# REACTION-CIRCUIT-DISPLAY.net
KiCad netlist of a schematic drawn in Altium Designer
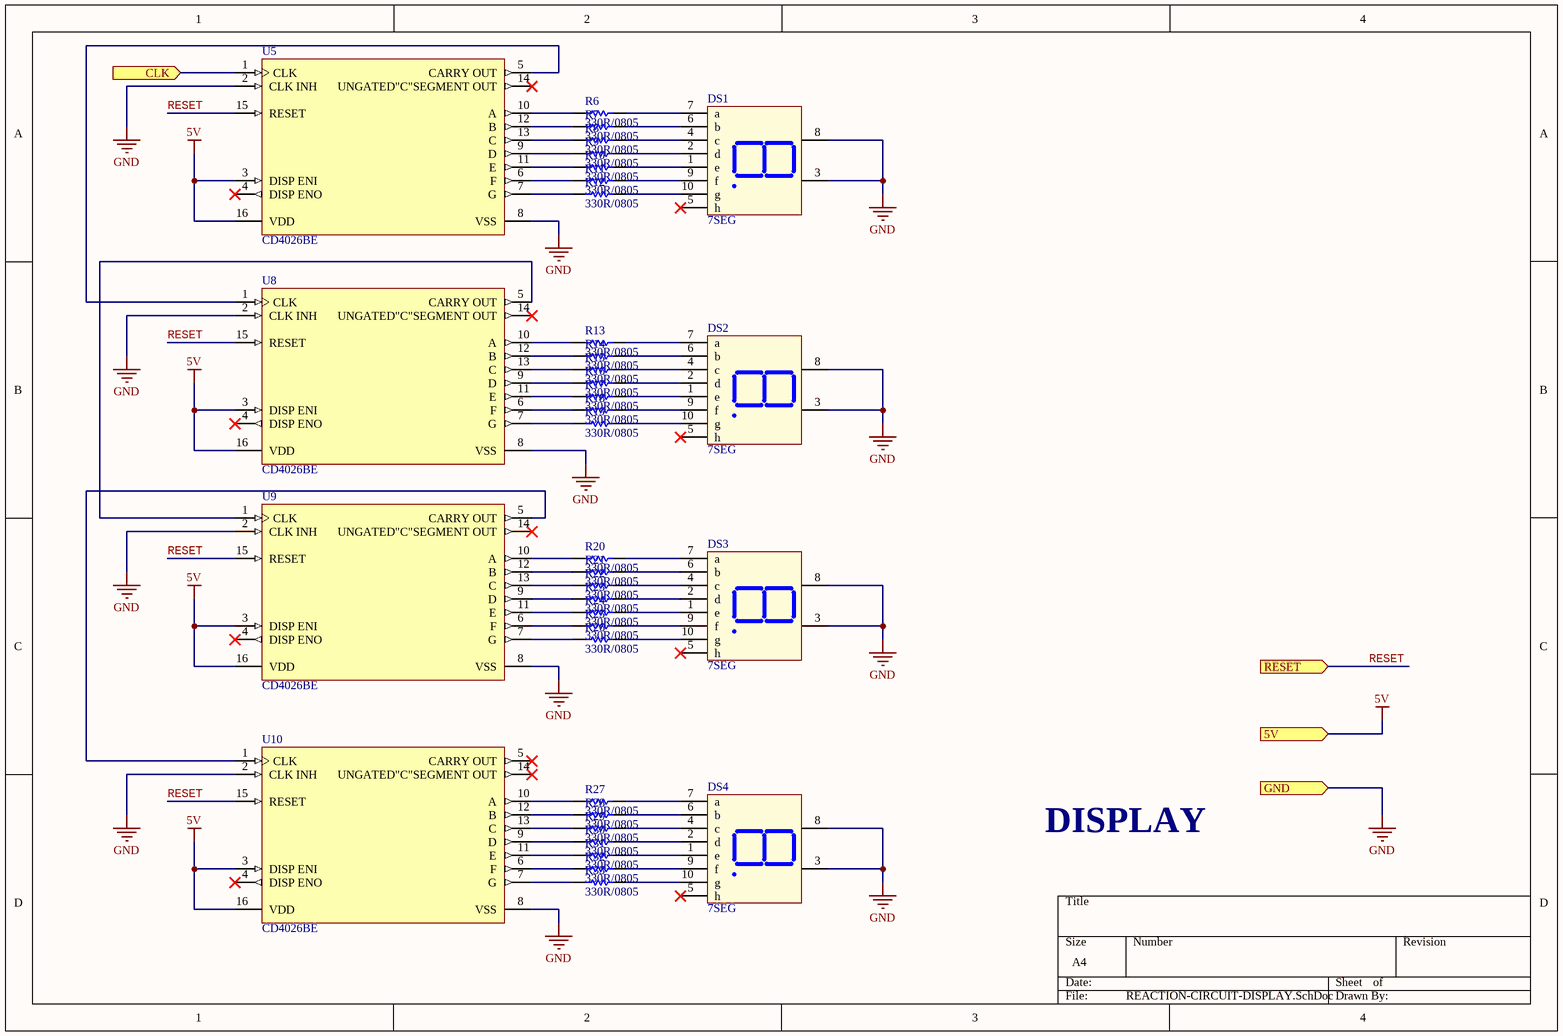
[diagram p0: REACTION-CIRCUIT-DISPLAY.SchDoc]

(export (version "E")
  (design (tool "Eeschema 10.0.6"))
  (components
    (comp (ref "DS1")
      (value "7SEG")
      (footprint "LED7SEG-1-0.56")
      (description "14.2 mm General Purpose Blue 7-Segment Display: CC, RH DP, Gray Surface")
      (fields (field (name "PUBLISHER") "Altium Limited"))
      (libsource (lib "LIBRARY_MuaLinhKien") (part "LED7SEG-1"))
    )
    (comp (ref "DS2")
      (value "7SEG")
      (footprint "LED7SEG-1-0.56")
      (description "14.2 mm General Purpose Blue 7-Segment Display: CC, RH DP, Gray Surface")
      (fields (field (name "PUBLISHER") "Altium Limited"))
      (libsource (lib "LIBRARY_MuaLinhKien") (part "LED7SEG-1"))
    )
    (comp (ref "DS3")
      (value "7SEG")
      (footprint "LED7SEG-1-0.56")
      (description "14.2 mm General Purpose Blue 7-Segment Display: CC, RH DP, Gray Surface")
      (fields (field (name "PUBLISHER") "Altium Limited"))
      (libsource (lib "LIBRARY_MuaLinhKien") (part "LED7SEG-1"))
    )
    (comp (ref "DS4")
      (value "7SEG")
      (footprint "LED7SEG-1-0.56")
      (description "14.2 mm General Purpose Blue 7-Segment Display: CC, RH DP, Gray Surface")
      (fields (field (name "PUBLISHER") "Altium Limited"))
      (libsource (lib "LIBRARY_MuaLinhKien") (part "LED7SEG-1"))
    )
    (comp (ref "R6")
      (value "330R/0805")
      (footprint "Res 0805(2012)")
      (description "Resistor 0805")
      (libsource (lib "Duc") (part "Resistor 0805"))
    )
    (comp (ref "R7")
      (value "330R/0805")
      (footprint "Res 0805(2012)")
      (description "Resistor 0805")
      (libsource (lib "Duc") (part "Resistor 0805"))
    )
    (comp (ref "R8")
      (value "330R/0805")
      (footprint "Res 0805(2012)")
      (description "Resistor 0805")
      (libsource (lib "Duc") (part "Resistor 0805"))
    )
    (comp (ref "R9")
      (value "330R/0805")
      (footprint "Res 0805(2012)")
      (description "Resistor 0805")
      (libsource (lib "Duc") (part "Resistor 0805"))
    )
    (comp (ref "R10")
      (value "330R/0805")
      (footprint "Res 0805(2012)")
      (description "Resistor 0805")
      (libsource (lib "Duc") (part "Resistor 0805"))
    )
    (comp (ref "R11")
      (value "330R/0805")
      (footprint "Res 0805(2012)")
      (description "Resistor 0805")
      (libsource (lib "Duc") (part "Resistor 0805"))
    )
    (comp (ref "R12")
      (value "330R/0805")
      (footprint "Res 0805(2012)")
      (description "Resistor 0805")
      (libsource (lib "Duc") (part "Resistor 0805"))
    )
    (comp (ref "R13")
      (value "330R/0805")
      (footprint "Res 0805(2012)")
      (description "Resistor 0805")
      (libsource (lib "Duc") (part "Resistor 0805"))
    )
    (comp (ref "R14")
      (value "330R/0805")
      (footprint "Res 0805(2012)")
      (description "Resistor 0805")
      (libsource (lib "Duc") (part "Resistor 0805"))
    )
    (comp (ref "R15")
      (value "330R/0805")
      (footprint "Res 0805(2012)")
      (description "Resistor 0805")
      (libsource (lib "Duc") (part "Resistor 0805"))
    )
    (comp (ref "R16")
      (value "330R/0805")
      (footprint "Res 0805(2012)")
      (description "Resistor 0805")
      (libsource (lib "Duc") (part "Resistor 0805"))
    )
    (comp (ref "R17")
      (value "330R/0805")
      (footprint "Res 0805(2012)")
      (description "Resistor 0805")
      (libsource (lib "Duc") (part "Resistor 0805"))
    )
    (comp (ref "R18")
      (value "330R/0805")
      (footprint "Res 0805(2012)")
      (description "Resistor 0805")
      (libsource (lib "Duc") (part "Resistor 0805"))
    )
    (comp (ref "R19")
      (value "330R/0805")
      (footprint "Res 0805(2012)")
      (description "Resistor 0805")
      (libsource (lib "Duc") (part "Resistor 0805"))
    )
    (comp (ref "R20")
      (value "330R/0805")
      (footprint "Res 0805(2012)")
      (description "Resistor 0805")
      (libsource (lib "Duc") (part "Resistor 0805"))
    )
    (comp (ref "R21")
      (value "330R/0805")
      (footprint "Res 0805(2012)")
      (description "Resistor 0805")
      (libsource (lib "Duc") (part "Resistor 0805"))
    )
    (comp (ref "R22")
      (value "330R/0805")
      (footprint "Res 0805(2012)")
      (description "Resistor 0805")
      (libsource (lib "Duc") (part "Resistor 0805"))
    )
    (comp (ref "R23")
      (value "330R/0805")
      (footprint "Res 0805(2012)")
      (description "Resistor 0805")
      (libsource (lib "Duc") (part "Resistor 0805"))
    )
    (comp (ref "R24")
      (value "330R/0805")
      (footprint "Res 0805(2012)")
      (description "Resistor 0805")
      (libsource (lib "Duc") (part "Resistor 0805"))
    )
    (comp (ref "R25")
      (value "330R/0805")
      (footprint "Res 0805(2012)")
      (description "Resistor 0805")
      (libsource (lib "Duc") (part "Resistor 0805"))
    )
    (comp (ref "R26")
      (value "330R/0805")
      (footprint "Res 0805(2012)")
      (description "Resistor 0805")
      (libsource (lib "Duc") (part "Resistor 0805"))
    )
    (comp (ref "R27")
      (value "330R/0805")
      (footprint "Res 0805(2012)")
      (description "Resistor 0805")
      (libsource (lib "Duc") (part "Resistor 0805"))
    )
    (comp (ref "R28")
      (value "330R/0805")
      (footprint "Res 0805(2012)")
      (description "Resistor 0805")
      (libsource (lib "Duc") (part "Resistor 0805"))
    )
    (comp (ref "R29")
      (value "330R/0805")
      (footprint "Res 0805(2012)")
      (description "Resistor 0805")
      (libsource (lib "Duc") (part "Resistor 0805"))
    )
    (comp (ref "R30")
      (value "330R/0805")
      (footprint "Res 0805(2012)")
      (description "Resistor 0805")
      (libsource (lib "Duc") (part "Resistor 0805"))
    )
    (comp (ref "R31")
      (value "330R/0805")
      (footprint "Res 0805(2012)")
      (description "Resistor 0805")
      (libsource (lib "Duc") (part "Resistor 0805"))
    )
    (comp (ref "R32")
      (value "330R/0805")
      (footprint "Res 0805(2012)")
      (description "Resistor 0805")
      (libsource (lib "Duc") (part "Resistor 0805"))
    )
    (comp (ref "R33")
      (value "330R/0805")
      (footprint "Res 0805(2012)")
      (description "Resistor 0805")
      (libsource (lib "Duc") (part "Resistor 0805"))
    )
    (comp (ref "U5")
      (value "CD4026BE")
      (footprint "N0016A")
      (fields
        (field (name "MANUFACTURER") "Texas Instruments")
        (field (name "GENERIC PART NUMBER") "CD4026B")
      )
      (libsource (lib "Altium Content Vault") (part "TI-CD4026B-16"))
    )
    (comp (ref "U8")
      (value "CD4026BE")
      (footprint "N0016A")
      (fields
        (field (name "MANUFACTURER") "Texas Instruments")
        (field (name "GENERIC PART NUMBER") "CD4026B")
      )
      (libsource (lib "Altium Content Vault") (part "TI-CD4026B-16"))
    )
    (comp (ref "U9")
      (value "CD4026BE")
      (footprint "N0016A")
      (fields
        (field (name "MANUFACTURER") "Texas Instruments")
        (field (name "GENERIC PART NUMBER") "CD4026B")
      )
      (libsource (lib "Altium Content Vault") (part "TI-CD4026B-16"))
    )
    (comp (ref "U10")
      (value "CD4026BE")
      (footprint "N0016A")
      (fields
        (field (name "MANUFACTURER") "Texas Instruments")
        (field (name "GENERIC PART NUMBER") "CD4026B")
      )
      (libsource (lib "Altium Content Vault") (part "TI-CD4026B-16"))
    )
  )
  (nets
    (net (code "1") (name "/CLK") (class "Default")
      (node (ref "U5") (pin "1") (pinfunction "CLK_1") (pintype "input"))
    )
    (net (code "2") (name "/RESET") (class "Default")
      (node (ref "U10") (pin "15") (pinfunction "RESET_15") (pintype "input"))
      (node (ref "U5") (pin "15") (pinfunction "RESET_15") (pintype "input"))
      (node (ref "U8") (pin "15") (pinfunction "RESET_15") (pintype "input"))
      (node (ref "U9") (pin "15") (pinfunction "RESET_15") (pintype "input"))
    )
    (net (code "3") (name "5V") (class "Default")
      (node (ref "U10") (pin "16") (pinfunction "VDD_16") (pintype "power_in"))
      (node (ref "U10") (pin "3") (pinfunction "DISP_ENI_3") (pintype "input"))
      (node (ref "U5") (pin "16") (pinfunction "VDD_16") (pintype "power_in"))
      (node (ref "U5") (pin "3") (pinfunction "DISP_ENI_3") (pintype "input"))
      (node (ref "U8") (pin "16") (pinfunction "VDD_16") (pintype "power_in"))
      (node (ref "U8") (pin "3") (pinfunction "DISP_ENI_3") (pintype "input"))
      (node (ref "U9") (pin "16") (pinfunction "VDD_16") (pintype "power_in"))
      (node (ref "U9") (pin "3") (pinfunction "DISP_ENI_3") (pintype "input"))
    )
    (net (code "4") (name "GND") (class "Default")
      (node (ref "DS1") (pin "3") (pinfunction "Vcc_3") (pintype "passive"))
      (node (ref "DS1") (pin "8") (pinfunction "Vcc_8") (pintype "passive"))
      (node (ref "DS2") (pin "3") (pinfunction "Vcc_3") (pintype "passive"))
      (node (ref "DS2") (pin "8") (pinfunction "Vcc_8") (pintype "passive"))
      (node (ref "DS3") (pin "3") (pinfunction "Vcc_3") (pintype "passive"))
      (node (ref "DS3") (pin "8") (pinfunction "Vcc_8") (pintype "passive"))
      (node (ref "DS4") (pin "3") (pinfunction "Vcc_3") (pintype "passive"))
      (node (ref "DS4") (pin "8") (pinfunction "Vcc_8") (pintype "passive"))
      (node (ref "U10") (pin "2") (pinfunction "CLK_INH_2") (pintype "input"))
      (node (ref "U10") (pin "8") (pinfunction "VSS_8") (pintype "power_in"))
      (node (ref "U5") (pin "2") (pinfunction "CLK_INH_2") (pintype "input"))
      (node (ref "U5") (pin "8") (pinfunction "VSS_8") (pintype "power_in"))
      (node (ref "U8") (pin "2") (pinfunction "CLK_INH_2") (pintype "input"))
      (node (ref "U8") (pin "8") (pinfunction "VSS_8") (pintype "power_in"))
      (node (ref "U9") (pin "2") (pinfunction "CLK_INH_2") (pintype "input"))
      (node (ref "U9") (pin "8") (pinfunction "VSS_8") (pintype "power_in"))
    )
    (net (code "5") (name "Net-(DS1-a)") (class "Default")
      (node (ref "DS1") (pin "7") (pinfunction "a_7") (pintype "passive"))
      (node (ref "R6") (pin "1") (pinfunction "1_1") (pintype "passive"))
    )
    (net (code "6") (name "Net-(DS1-b)") (class "Default")
      (node (ref "DS1") (pin "6") (pinfunction "b_6") (pintype "passive"))
      (node (ref "R7") (pin "1") (pinfunction "1_1") (pintype "passive"))
    )
    (net (code "7") (name "Net-(DS1-c)") (class "Default")
      (node (ref "DS1") (pin "4") (pinfunction "c_4") (pintype "passive"))
      (node (ref "R8") (pin "1") (pinfunction "1_1") (pintype "passive"))
    )
    (net (code "8") (name "Net-(DS1-d)") (class "Default")
      (node (ref "DS1") (pin "2") (pinfunction "d_2") (pintype "passive"))
      (node (ref "R9") (pin "1") (pinfunction "1_1") (pintype "passive"))
    )
    (net (code "9") (name "Net-(DS1-e)") (class "Default")
      (node (ref "DS1") (pin "1") (pinfunction "e_1") (pintype "passive"))
      (node (ref "R10") (pin "1") (pinfunction "1_1") (pintype "passive"))
    )
    (net (code "10") (name "Net-(DS1-f)") (class "Default")
      (node (ref "DS1") (pin "9") (pinfunction "f_9") (pintype "passive"))
      (node (ref "R11") (pin "1") (pinfunction "1_1") (pintype "passive"))
    )
    (net (code "11") (name "Net-(DS1-g)") (class "Default")
      (node (ref "DS1") (pin "10") (pinfunction "g_10") (pintype "passive"))
      (node (ref "R12") (pin "1") (pinfunction "1_1") (pintype "passive"))
    )
    (net (code "12") (name "Net-(DS2-a)") (class "Default")
      (node (ref "DS2") (pin "7") (pinfunction "a_7") (pintype "passive"))
      (node (ref "R13") (pin "1") (pinfunction "1_1") (pintype "passive"))
    )
    (net (code "13") (name "Net-(DS2-b)") (class "Default")
      (node (ref "DS2") (pin "6") (pinfunction "b_6") (pintype "passive"))
      (node (ref "R14") (pin "1") (pinfunction "1_1") (pintype "passive"))
    )
    (net (code "14") (name "Net-(DS2-c)") (class "Default")
      (node (ref "DS2") (pin "4") (pinfunction "c_4") (pintype "passive"))
      (node (ref "R15") (pin "1") (pinfunction "1_1") (pintype "passive"))
    )
    (net (code "15") (name "Net-(DS2-d)") (class "Default")
      (node (ref "DS2") (pin "2") (pinfunction "d_2") (pintype "passive"))
      (node (ref "R16") (pin "1") (pinfunction "1_1") (pintype "passive"))
    )
    (net (code "16") (name "Net-(DS2-e)") (class "Default")
      (node (ref "DS2") (pin "1") (pinfunction "e_1") (pintype "passive"))
      (node (ref "R17") (pin "1") (pinfunction "1_1") (pintype "passive"))
    )
    (net (code "17") (name "Net-(DS2-f)") (class "Default")
      (node (ref "DS2") (pin "9") (pinfunction "f_9") (pintype "passive"))
      (node (ref "R18") (pin "1") (pinfunction "1_1") (pintype "passive"))
    )
    (net (code "18") (name "Net-(DS2-g)") (class "Default")
      (node (ref "DS2") (pin "10") (pinfunction "g_10") (pintype "passive"))
      (node (ref "R19") (pin "1") (pinfunction "1_1") (pintype "passive"))
    )
    (net (code "19") (name "Net-(DS3-a)") (class "Default")
      (node (ref "DS3") (pin "7") (pinfunction "a_7") (pintype "passive"))
      (node (ref "R20") (pin "1") (pinfunction "1_1") (pintype "passive"))
    )
    (net (code "20") (name "Net-(DS3-b)") (class "Default")
      (node (ref "DS3") (pin "6") (pinfunction "b_6") (pintype "passive"))
      (node (ref "R21") (pin "1") (pinfunction "1_1") (pintype "passive"))
    )
    (net (code "21") (name "Net-(DS3-c)") (class "Default")
      (node (ref "DS3") (pin "4") (pinfunction "c_4") (pintype "passive"))
      (node (ref "R22") (pin "1") (pinfunction "1_1") (pintype "passive"))
    )
    (net (code "22") (name "Net-(DS3-d)") (class "Default")
      (node (ref "DS3") (pin "2") (pinfunction "d_2") (pintype "passive"))
      (node (ref "R23") (pin "1") (pinfunction "1_1") (pintype "passive"))
    )
    (net (code "23") (name "Net-(DS3-e)") (class "Default")
      (node (ref "DS3") (pin "1") (pinfunction "e_1") (pintype "passive"))
      (node (ref "R24") (pin "1") (pinfunction "1_1") (pintype "passive"))
    )
    (net (code "24") (name "Net-(DS3-f)") (class "Default")
      (node (ref "DS3") (pin "9") (pinfunction "f_9") (pintype "passive"))
      (node (ref "R25") (pin "1") (pinfunction "1_1") (pintype "passive"))
    )
    (net (code "25") (name "Net-(DS3-g)") (class "Default")
      (node (ref "DS3") (pin "10") (pinfunction "g_10") (pintype "passive"))
      (node (ref "R26") (pin "1") (pinfunction "1_1") (pintype "passive"))
    )
    (net (code "26") (name "Net-(DS4-a)") (class "Default")
      (node (ref "DS4") (pin "7") (pinfunction "a_7") (pintype "passive"))
      (node (ref "R27") (pin "1") (pinfunction "1_1") (pintype "passive"))
    )
    (net (code "27") (name "Net-(DS4-b)") (class "Default")
      (node (ref "DS4") (pin "6") (pinfunction "b_6") (pintype "passive"))
      (node (ref "R28") (pin "1") (pinfunction "1_1") (pintype "passive"))
    )
    (net (code "28") (name "Net-(DS4-c)") (class "Default")
      (node (ref "DS4") (pin "4") (pinfunction "c_4") (pintype "passive"))
      (node (ref "R29") (pin "1") (pinfunction "1_1") (pintype "passive"))
    )
    (net (code "29") (name "Net-(DS4-d)") (class "Default")
      (node (ref "DS4") (pin "2") (pinfunction "d_2") (pintype "passive"))
      (node (ref "R30") (pin "1") (pinfunction "1_1") (pintype "passive"))
    )
    (net (code "30") (name "Net-(DS4-e)") (class "Default")
      (node (ref "DS4") (pin "1") (pinfunction "e_1") (pintype "passive"))
      (node (ref "R31") (pin "1") (pinfunction "1_1") (pintype "passive"))
    )
    (net (code "31") (name "Net-(DS4-f)") (class "Default")
      (node (ref "DS4") (pin "9") (pinfunction "f_9") (pintype "passive"))
      (node (ref "R32") (pin "1") (pinfunction "1_1") (pintype "passive"))
    )
    (net (code "32") (name "Net-(DS4-g)") (class "Default")
      (node (ref "DS4") (pin "10") (pinfunction "g_10") (pintype "passive"))
      (node (ref "R33") (pin "1") (pinfunction "1_1") (pintype "passive"))
    )
    (net (code "33") (name "Net-(U5-A)") (class "Default")
      (node (ref "R6") (pin "2") (pinfunction "2_2") (pintype "passive"))
      (node (ref "U5") (pin "10") (pinfunction "A_10") (pintype "output"))
    )
    (net (code "34") (name "Net-(U5-B)") (class "Default")
      (node (ref "R7") (pin "2") (pinfunction "2_2") (pintype "passive"))
      (node (ref "U5") (pin "12") (pinfunction "B_12") (pintype "output"))
    )
    (net (code "35") (name "Net-(U5-C)") (class "Default")
      (node (ref "R8") (pin "2") (pinfunction "2_2") (pintype "passive"))
      (node (ref "U5") (pin "13") (pinfunction "C_13") (pintype "output"))
    )
    (net (code "36") (name "Net-(U5-CARRY_OUT)") (class "Default")
      (node (ref "U5") (pin "5") (pinfunction "CARRY_OUT_5") (pintype "output"))
      (node (ref "U8") (pin "1") (pinfunction "CLK_1") (pintype "input"))
    )
    (net (code "37") (name "Net-(U5-D)") (class "Default")
      (node (ref "R9") (pin "2") (pinfunction "2_2") (pintype "passive"))
      (node (ref "U5") (pin "9") (pinfunction "D_9") (pintype "output"))
    )
    (net (code "38") (name "Net-(U5-E)") (class "Default")
      (node (ref "R10") (pin "2") (pinfunction "2_2") (pintype "passive"))
      (node (ref "U5") (pin "11") (pinfunction "E_11") (pintype "output"))
    )
    (net (code "39") (name "Net-(U5-F)") (class "Default")
      (node (ref "R11") (pin "2") (pinfunction "2_2") (pintype "passive"))
      (node (ref "U5") (pin "6") (pinfunction "F_6") (pintype "output"))
    )
    (net (code "40") (name "Net-(U5-G)") (class "Default")
      (node (ref "R12") (pin "2") (pinfunction "2_2") (pintype "passive"))
      (node (ref "U5") (pin "7") (pinfunction "G_7") (pintype "output"))
    )
    (net (code "41") (name "Net-(U8-A)") (class "Default")
      (node (ref "R13") (pin "2") (pinfunction "2_2") (pintype "passive"))
      (node (ref "U8") (pin "10") (pinfunction "A_10") (pintype "output"))
    )
    (net (code "42") (name "Net-(U8-B)") (class "Default")
      (node (ref "R14") (pin "2") (pinfunction "2_2") (pintype "passive"))
      (node (ref "U8") (pin "12") (pinfunction "B_12") (pintype "output"))
    )
    (net (code "43") (name "Net-(U8-C)") (class "Default")
      (node (ref "R15") (pin "2") (pinfunction "2_2") (pintype "passive"))
      (node (ref "U8") (pin "13") (pinfunction "C_13") (pintype "output"))
    )
    (net (code "44") (name "Net-(U8-CARRY_OUT)") (class "Default")
      (node (ref "U8") (pin "5") (pinfunction "CARRY_OUT_5") (pintype "output"))
      (node (ref "U9") (pin "1") (pinfunction "CLK_1") (pintype "input"))
    )
    (net (code "45") (name "Net-(U8-D)") (class "Default")
      (node (ref "R16") (pin "2") (pinfunction "2_2") (pintype "passive"))
      (node (ref "U8") (pin "9") (pinfunction "D_9") (pintype "output"))
    )
    (net (code "46") (name "Net-(U8-E)") (class "Default")
      (node (ref "R17") (pin "2") (pinfunction "2_2") (pintype "passive"))
      (node (ref "U8") (pin "11") (pinfunction "E_11") (pintype "output"))
    )
    (net (code "47") (name "Net-(U8-F)") (class "Default")
      (node (ref "R18") (pin "2") (pinfunction "2_2") (pintype "passive"))
      (node (ref "U8") (pin "6") (pinfunction "F_6") (pintype "output"))
    )
    (net (code "48") (name "Net-(U8-G)") (class "Default")
      (node (ref "R19") (pin "2") (pinfunction "2_2") (pintype "passive"))
      (node (ref "U8") (pin "7") (pinfunction "G_7") (pintype "output"))
    )
    (net (code "49") (name "Net-(U9-A)") (class "Default")
      (node (ref "R20") (pin "2") (pinfunction "2_2") (pintype "passive"))
      (node (ref "U9") (pin "10") (pinfunction "A_10") (pintype "output"))
    )
    (net (code "50") (name "Net-(U9-B)") (class "Default")
      (node (ref "R21") (pin "2") (pinfunction "2_2") (pintype "passive"))
      (node (ref "U9") (pin "12") (pinfunction "B_12") (pintype "output"))
    )
    (net (code "51") (name "Net-(U9-C)") (class "Default")
      (node (ref "R22") (pin "2") (pinfunction "2_2") (pintype "passive"))
      (node (ref "U9") (pin "13") (pinfunction "C_13") (pintype "output"))
    )
    (net (code "52") (name "Net-(U9-D)") (class "Default")
      (node (ref "R23") (pin "2") (pinfunction "2_2") (pintype "passive"))
      (node (ref "U9") (pin "9") (pinfunction "D_9") (pintype "output"))
    )
    (net (code "53") (name "Net-(U9-E)") (class "Default")
      (node (ref "R24") (pin "2") (pinfunction "2_2") (pintype "passive"))
      (node (ref "U9") (pin "11") (pinfunction "E_11") (pintype "output"))
    )
    (net (code "54") (name "Net-(U9-F)") (class "Default")
      (node (ref "R25") (pin "2") (pinfunction "2_2") (pintype "passive"))
      (node (ref "U9") (pin "6") (pinfunction "F_6") (pintype "output"))
    )
    (net (code "55") (name "Net-(U9-G)") (class "Default")
      (node (ref "R26") (pin "2") (pinfunction "2_2") (pintype "passive"))
      (node (ref "U9") (pin "7") (pinfunction "G_7") (pintype "output"))
    )
    (net (code "56") (name "Net-(U10-A)") (class "Default")
      (node (ref "R27") (pin "2") (pinfunction "2_2") (pintype "passive"))
      (node (ref "U10") (pin "10") (pinfunction "A_10") (pintype "output"))
    )
    (net (code "57") (name "Net-(U10-B)") (class "Default")
      (node (ref "R28") (pin "2") (pinfunction "2_2") (pintype "passive"))
      (node (ref "U10") (pin "12") (pinfunction "B_12") (pintype "output"))
    )
    (net (code "58") (name "Net-(U10-C)") (class "Default")
      (node (ref "R29") (pin "2") (pinfunction "2_2") (pintype "passive"))
      (node (ref "U10") (pin "13") (pinfunction "C_13") (pintype "output"))
    )
    (net (code "59") (name "Net-(U10-CLK)") (class "Default")
      (node (ref "U10") (pin "1") (pinfunction "CLK_1") (pintype "input"))
      (node (ref "U9") (pin "5") (pinfunction "CARRY_OUT_5") (pintype "output"))
    )
    (net (code "60") (name "Net-(U10-D)") (class "Default")
      (node (ref "R30") (pin "2") (pinfunction "2_2") (pintype "passive"))
      (node (ref "U10") (pin "9") (pinfunction "D_9") (pintype "output"))
    )
    (net (code "61") (name "Net-(U10-E)") (class "Default")
      (node (ref "R31") (pin "2") (pinfunction "2_2") (pintype "passive"))
      (node (ref "U10") (pin "11") (pinfunction "E_11") (pintype "output"))
    )
    (net (code "62") (name "Net-(U10-F)") (class "Default")
      (node (ref "R32") (pin "2") (pinfunction "2_2") (pintype "passive"))
      (node (ref "U10") (pin "6") (pinfunction "F_6") (pintype "output"))
    )
    (net (code "63") (name "Net-(U10-G)") (class "Default")
      (node (ref "R33") (pin "2") (pinfunction "2_2") (pintype "passive"))
      (node (ref "U10") (pin "7") (pinfunction "G_7") (pintype "output"))
    )
    (net (code "64") (name "unconnected-(DS1-h-Pad5)") (class "Default")
      (node (ref "DS1") (pin "5") (pinfunction "h_5") (pintype "passive+no_connect"))
    )
    (net (code "65") (name "unconnected-(DS2-h-Pad5)") (class "Default")
      (node (ref "DS2") (pin "5") (pinfunction "h_5") (pintype "passive+no_connect"))
    )
    (net (code "66") (name "unconnected-(DS3-h-Pad5)") (class "Default")
      (node (ref "DS3") (pin "5") (pinfunction "h_5") (pintype "passive+no_connect"))
    )
    (net (code "67") (name "unconnected-(DS4-h-Pad5)") (class "Default")
      (node (ref "DS4") (pin "5") (pinfunction "h_5") (pintype "passive+no_connect"))
    )
    (net (code "68") (name "unconnected-(U5-DISP_ENO-Pad4)") (class "Default")
      (node (ref "U5") (pin "4") (pinfunction "DISP_ENO_4") (pintype "output+no_connect"))
    )
    (net (code "69") (name "unconnected-(U5-UNGATED\"C\"SEGMENT_OUT-Pad14)") (class "Default")
      (node (ref "U5") (pin "14") (pinfunction "UNGATED\"C\"SEGMENT_OUT_14") (pintype "output+no_connect"))
    )
    (net (code "70") (name "unconnected-(U8-DISP_ENO-Pad4)") (class "Default")
      (node (ref "U8") (pin "4") (pinfunction "DISP_ENO_4") (pintype "output+no_connect"))
    )
    (net (code "71") (name "unconnected-(U8-UNGATED\"C\"SEGMENT_OUT-Pad14)") (class "Default")
      (node (ref "U8") (pin "14") (pinfunction "UNGATED\"C\"SEGMENT_OUT_14") (pintype "output+no_connect"))
    )
    (net (code "72") (name "unconnected-(U9-DISP_ENO-Pad4)") (class "Default")
      (node (ref "U9") (pin "4") (pinfunction "DISP_ENO_4") (pintype "output+no_connect"))
    )
    (net (code "73") (name "unconnected-(U9-UNGATED\"C\"SEGMENT_OUT-Pad14)") (class "Default")
      (node (ref "U9") (pin "14") (pinfunction "UNGATED\"C\"SEGMENT_OUT_14") (pintype "output+no_connect"))
    )
    (net (code "74") (name "unconnected-(U10-CARRY_OUT-Pad5)") (class "Default")
      (node (ref "U10") (pin "5") (pinfunction "CARRY_OUT_5") (pintype "output+no_connect"))
    )
    (net (code "75") (name "unconnected-(U10-DISP_ENO-Pad4)") (class "Default")
      (node (ref "U10") (pin "4") (pinfunction "DISP_ENO_4") (pintype "output+no_connect"))
    )
    (net (code "76") (name "unconnected-(U10-UNGATED\"C\"SEGMENT_OUT-Pad14)") (class "Default")
      (node (ref "U10") (pin "14") (pinfunction "UNGATED\"C\"SEGMENT_OUT_14") (pintype "output+no_connect"))
    )
  )
)
